# uart-back1.net
KiCad netlist of a schematic drawn in EAGLE
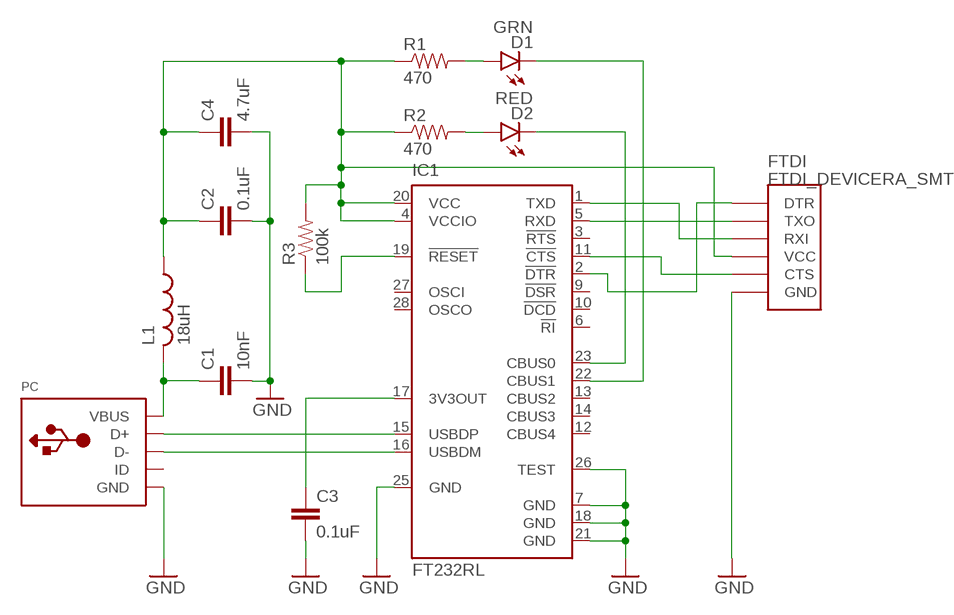
[diagram p0: schematic, sheet 1]

(export (version "E")
  (design (tool "Eeschema 10.0.6"))
  (components
    (comp (ref "C1")
      (value "10nF")
      (footprint "eagle-import:0603-CAP")
      (fields (field (name "MPN") "C0603C103J1RACTU"))
      (libsource (lib "eagle-import") (part "10NF/10000PF-50V-10%(0603)"))
    )
    (comp (ref "C2")
      (value "0.1uF")
      (footprint "eagle-import:0603-CAP")
      (fields (field (name "MPN") "C0603C104K4RAC7081"))
      (libsource (lib "eagle-import") (part "0.1UF-25V-5%(0603)"))
    )
    (comp (ref "C3")
      (value "0.1uF")
      (footprint "eagle-import:0603-CAP")
      (fields (field (name "MPN") "C0603C104K4RAC7081"))
      (libsource (lib "eagle-import") (part "0.1UF-25V-5%(0603)"))
    )
    (comp (ref "C4")
      (value "4.7uF")
      (footprint "eagle-import:0603-CAP")
      (fields (field (name "MPN") "0603F475Z100CT"))
      (libsource (lib "eagle-import") (part "4.7UF-6.3V-10%(0603)0603"))
    )
    (comp (ref "D1")
      (value "GRN")
      (footprint "eagle-import:LED-0603")
      (fields (field (name "MPN") "HSME-C191"))
      (libsource (lib "eagle-import") (part "LED-GREEN0603"))
    )
    (comp (ref "D2")
      (value "RED")
      (footprint "eagle-import:LED-0603")
      (fields (field (name "MPN") "HSMC-C120"))
      (libsource (lib "eagle-import") (part "LED-RED0603"))
    )
    (comp (ref "FTDI")
      (value "FTDI_DEVICERA_SMT")
      (footprint "eagle-import:FTDI_DEVICE_RA_SMT")
      (libsource (lib "eagle-import") (part "FTDI_DEVICERA_SMT"))
    )
    (comp (ref "IC1")
      (value "FT232RL")
      (footprint "eagle-import:SSOP28")
      (fields (field (name "MPN") "FT232RL-REEL"))
      (libsource (lib "eagle-import") (part "FT232RL"))
    )
    (comp (ref "L1")
      (value "18uH")
      (footprint "eagle-import:POWER-CHOKE_WE-TPC")
      (fields (field (name "MPN") "744052180"))
      (libsource (lib "eagle-import") (part "L-USWE-TPC"))
    )
    (comp (ref "PC")
      (value "USBMINIB")
      (footprint "eagle-import:USB-MINIB")
      (fields (field (name "MPN") "MUSB-B5-S-RA-TSMT-CS1"))
      (libsource (lib "eagle-import") (part "USBMINIB"))
    )
    (comp (ref "R1")
      (value "470")
      (footprint "eagle-import:0603-RES")
      (fields (field (name "MPN") "ERJ-P03F4700V"))
      (libsource (lib "eagle-import") (part "470OHM1/10W1%(0603)"))
    )
    (comp (ref "R2")
      (value "470")
      (footprint "eagle-import:0603-RES")
      (fields (field (name "MPN") "ERJ-P03F4700V"))
      (libsource (lib "eagle-import") (part "470OHM1/10W1%(0603)"))
    )
    (comp (ref "R3")
      (value "100k")
      (footprint "eagle-import:0603-RES")
      (fields (field (name "MPN") "ERA-3AEB104V"))
      (libsource (lib "eagle-import") (part "100KOHM-1/10W-1%(0603)"))
    )
  )
  (nets
    (net (code "1") (name "GND") (class "Default")
      (node (ref "C1") (pin "2") (pinfunction "2_2") (pintype "passive"))
      (node (ref "C2") (pin "2") (pinfunction "2_2") (pintype "passive"))
      (node (ref "C3") (pin "2") (pinfunction "2_2") (pintype "passive"))
      (node (ref "C4") (pin "2") (pinfunction "2_2") (pintype "passive"))
      (node (ref "FTDI") (pin "6") (pinfunction "GND_6") (pintype "bidirectional"))
      (node (ref "IC1") (pin "18") (pinfunction "GND_18") (pintype "power_in"))
      (node (ref "IC1") (pin "21") (pinfunction "GND_21") (pintype "power_in"))
      (node (ref "IC1") (pin "25") (pinfunction "GND_25") (pintype "power_in"))
      (node (ref "IC1") (pin "26") (pinfunction "TEST_26") (pintype "input"))
      (node (ref "IC1") (pin "7") (pinfunction "GND_7") (pintype "power_in"))
      (node (ref "PC") (pin "GND") (pinfunction "GND_GND") (pintype "power_in"))
    )
    (net (code "2") (name "Net-(C1-Pad1)") (class "Default")
      (node (ref "C1") (pin "1") (pinfunction "1_1") (pintype "passive"))
      (node (ref "L1") (pin "2") (pinfunction "2_2") (pintype "passive"))
      (node (ref "PC") (pin "VBUS") (pinfunction "VBUS_VBUS") (pintype "power_in"))
    )
    (net (code "3") (name "Net-(D1-PadA)") (class "Default")
      (node (ref "D1") (pin "A") (pinfunction "A_A") (pintype "passive"))
      (node (ref "R1") (pin "2") (pinfunction "2_2") (pintype "passive"))
    )
    (net (code "4") (name "Net-(D2-PadA)") (class "Default")
      (node (ref "D2") (pin "A") (pinfunction "A_A") (pintype "passive"))
      (node (ref "R2") (pin "2") (pinfunction "2_2") (pintype "passive"))
    )
    (net (code "5") (name "Net-(FTDI-CTS)") (class "Default")
      (node (ref "FTDI") (pin "5") (pinfunction "CTS_5") (pintype "bidirectional"))
      (node (ref "IC1") (pin "11") (pinfunction "~{CTS}_11") (pintype "input"))
    )
    (net (code "6") (name "Net-(FTDI-DTR)") (class "Default")
      (node (ref "FTDI") (pin "1") (pinfunction "DTR_1") (pintype "bidirectional"))
      (node (ref "IC1") (pin "2") (pinfunction "~{DTR}_2") (pintype "output"))
    )
    (net (code "7") (name "Net-(FTDI-RXI)") (class "Default")
      (node (ref "FTDI") (pin "3") (pinfunction "RXI_3") (pintype "bidirectional"))
      (node (ref "IC1") (pin "1") (pinfunction "TXD_1") (pintype "output"))
    )
    (net (code "8") (name "Net-(FTDI-TXO)") (class "Default")
      (node (ref "FTDI") (pin "2") (pinfunction "TXO_2") (pintype "bidirectional"))
      (node (ref "IC1") (pin "5") (pinfunction "RXD_5") (pintype "input"))
    )
    (net (code "9") (name "Net-(FTDI-VCC)") (class "Default")
      (node (ref "C2") (pin "1") (pinfunction "1_1") (pintype "passive"))
      (node (ref "C4") (pin "1") (pinfunction "1_1") (pintype "passive"))
      (node (ref "FTDI") (pin "4") (pinfunction "VCC_4") (pintype "bidirectional"))
      (node (ref "IC1") (pin "20") (pinfunction "VCC_20") (pintype "power_in"))
      (node (ref "IC1") (pin "4") (pinfunction "VCCIO_4") (pintype "power_in"))
      (node (ref "L1") (pin "1") (pinfunction "1_1") (pintype "passive"))
      (node (ref "R1") (pin "1") (pinfunction "1_1") (pintype "passive"))
      (node (ref "R2") (pin "1") (pinfunction "1_1") (pintype "passive"))
      (node (ref "R3") (pin "2") (pinfunction "2_2") (pintype "passive"))
    )
    (net (code "10") (name "Net-(IC1-3V3OUT)") (class "Default")
      (node (ref "C3") (pin "1") (pinfunction "1_1") (pintype "passive"))
      (node (ref "IC1") (pin "17") (pinfunction "3V3OUT_17") (pintype "output"))
    )
    (net (code "11") (name "Net-(IC1-CBUS0)") (class "Default")
      (node (ref "D2") (pin "C") (pinfunction "C_C") (pintype "passive"))
      (node (ref "IC1") (pin "23") (pinfunction "CBUS0_23") (pintype "bidirectional"))
    )
    (net (code "12") (name "Net-(IC1-CBUS1)") (class "Default")
      (node (ref "D1") (pin "C") (pinfunction "C_C") (pintype "passive"))
      (node (ref "IC1") (pin "22") (pinfunction "CBUS1_22") (pintype "bidirectional"))
    )
    (net (code "13") (name "Net-(IC1-USBDM)") (class "Default")
      (node (ref "IC1") (pin "16") (pinfunction "USBDM_16") (pintype "bidirectional"))
      (node (ref "PC") (pin "D-") (pinfunction "D-_D-") (pintype "bidirectional"))
    )
    (net (code "14") (name "Net-(IC1-USBDP)") (class "Default")
      (node (ref "IC1") (pin "15") (pinfunction "USBDP_15") (pintype "bidirectional"))
      (node (ref "PC") (pin "D+") (pinfunction "D+_D+") (pintype "bidirectional"))
    )
    (net (code "15") (name "Net-(IC1-~{RESET})") (class "Default")
      (node (ref "IC1") (pin "19") (pinfunction "~{RESET}_19") (pintype "input"))
      (node (ref "R3") (pin "1") (pinfunction "1_1") (pintype "passive"))
    )
    (net (code "16") (name "unconnected-(IC1-CBUS2-Pad13)") (class "Default")
      (node (ref "IC1") (pin "13") (pinfunction "CBUS2_13") (pintype "bidirectional"))
    )
    (net (code "17") (name "unconnected-(IC1-CBUS3-Pad14)") (class "Default")
      (node (ref "IC1") (pin "14") (pinfunction "CBUS3_14") (pintype "bidirectional"))
    )
    (net (code "18") (name "unconnected-(IC1-CBUS4-Pad12)") (class "Default")
      (node (ref "IC1") (pin "12") (pinfunction "CBUS4_12") (pintype "bidirectional"))
    )
    (net (code "19") (name "unconnected-(IC1-OSCI-Pad27)") (class "Default")
      (node (ref "IC1") (pin "27") (pinfunction "OSCI_27") (pintype "input"))
    )
    (net (code "20") (name "unconnected-(IC1-OSCO-Pad28)") (class "Default")
      (node (ref "IC1") (pin "28") (pinfunction "OSCO_28") (pintype "output"))
    )
    (net (code "21") (name "unconnected-(IC1-~{DCD}-Pad10)") (class "Default")
      (node (ref "IC1") (pin "10") (pinfunction "~{DCD}_10") (pintype "input"))
    )
    (net (code "22") (name "unconnected-(IC1-~{DSR}-Pad9)") (class "Default")
      (node (ref "IC1") (pin "9") (pinfunction "~{DSR}_9") (pintype "input"))
    )
    (net (code "23") (name "unconnected-(IC1-~{RI}-Pad6)") (class "Default")
      (node (ref "IC1") (pin "6") (pinfunction "~{RI}_6") (pintype "input"))
    )
    (net (code "24") (name "unconnected-(IC1-~{RTS}-Pad3)") (class "Default")
      (node (ref "IC1") (pin "3") (pinfunction "~{RTS}_3") (pintype "output"))
    )
    (net (code "25") (name "unconnected-(PC-PadID)") (class "Default")
      (node (ref "PC") (pin "ID") (pinfunction "ID_ID") (pintype "bidirectional"))
    )
  )
)
